# CH32V407VET-R0.net
KiCad netlist of a schematic drawn in Altium Designer
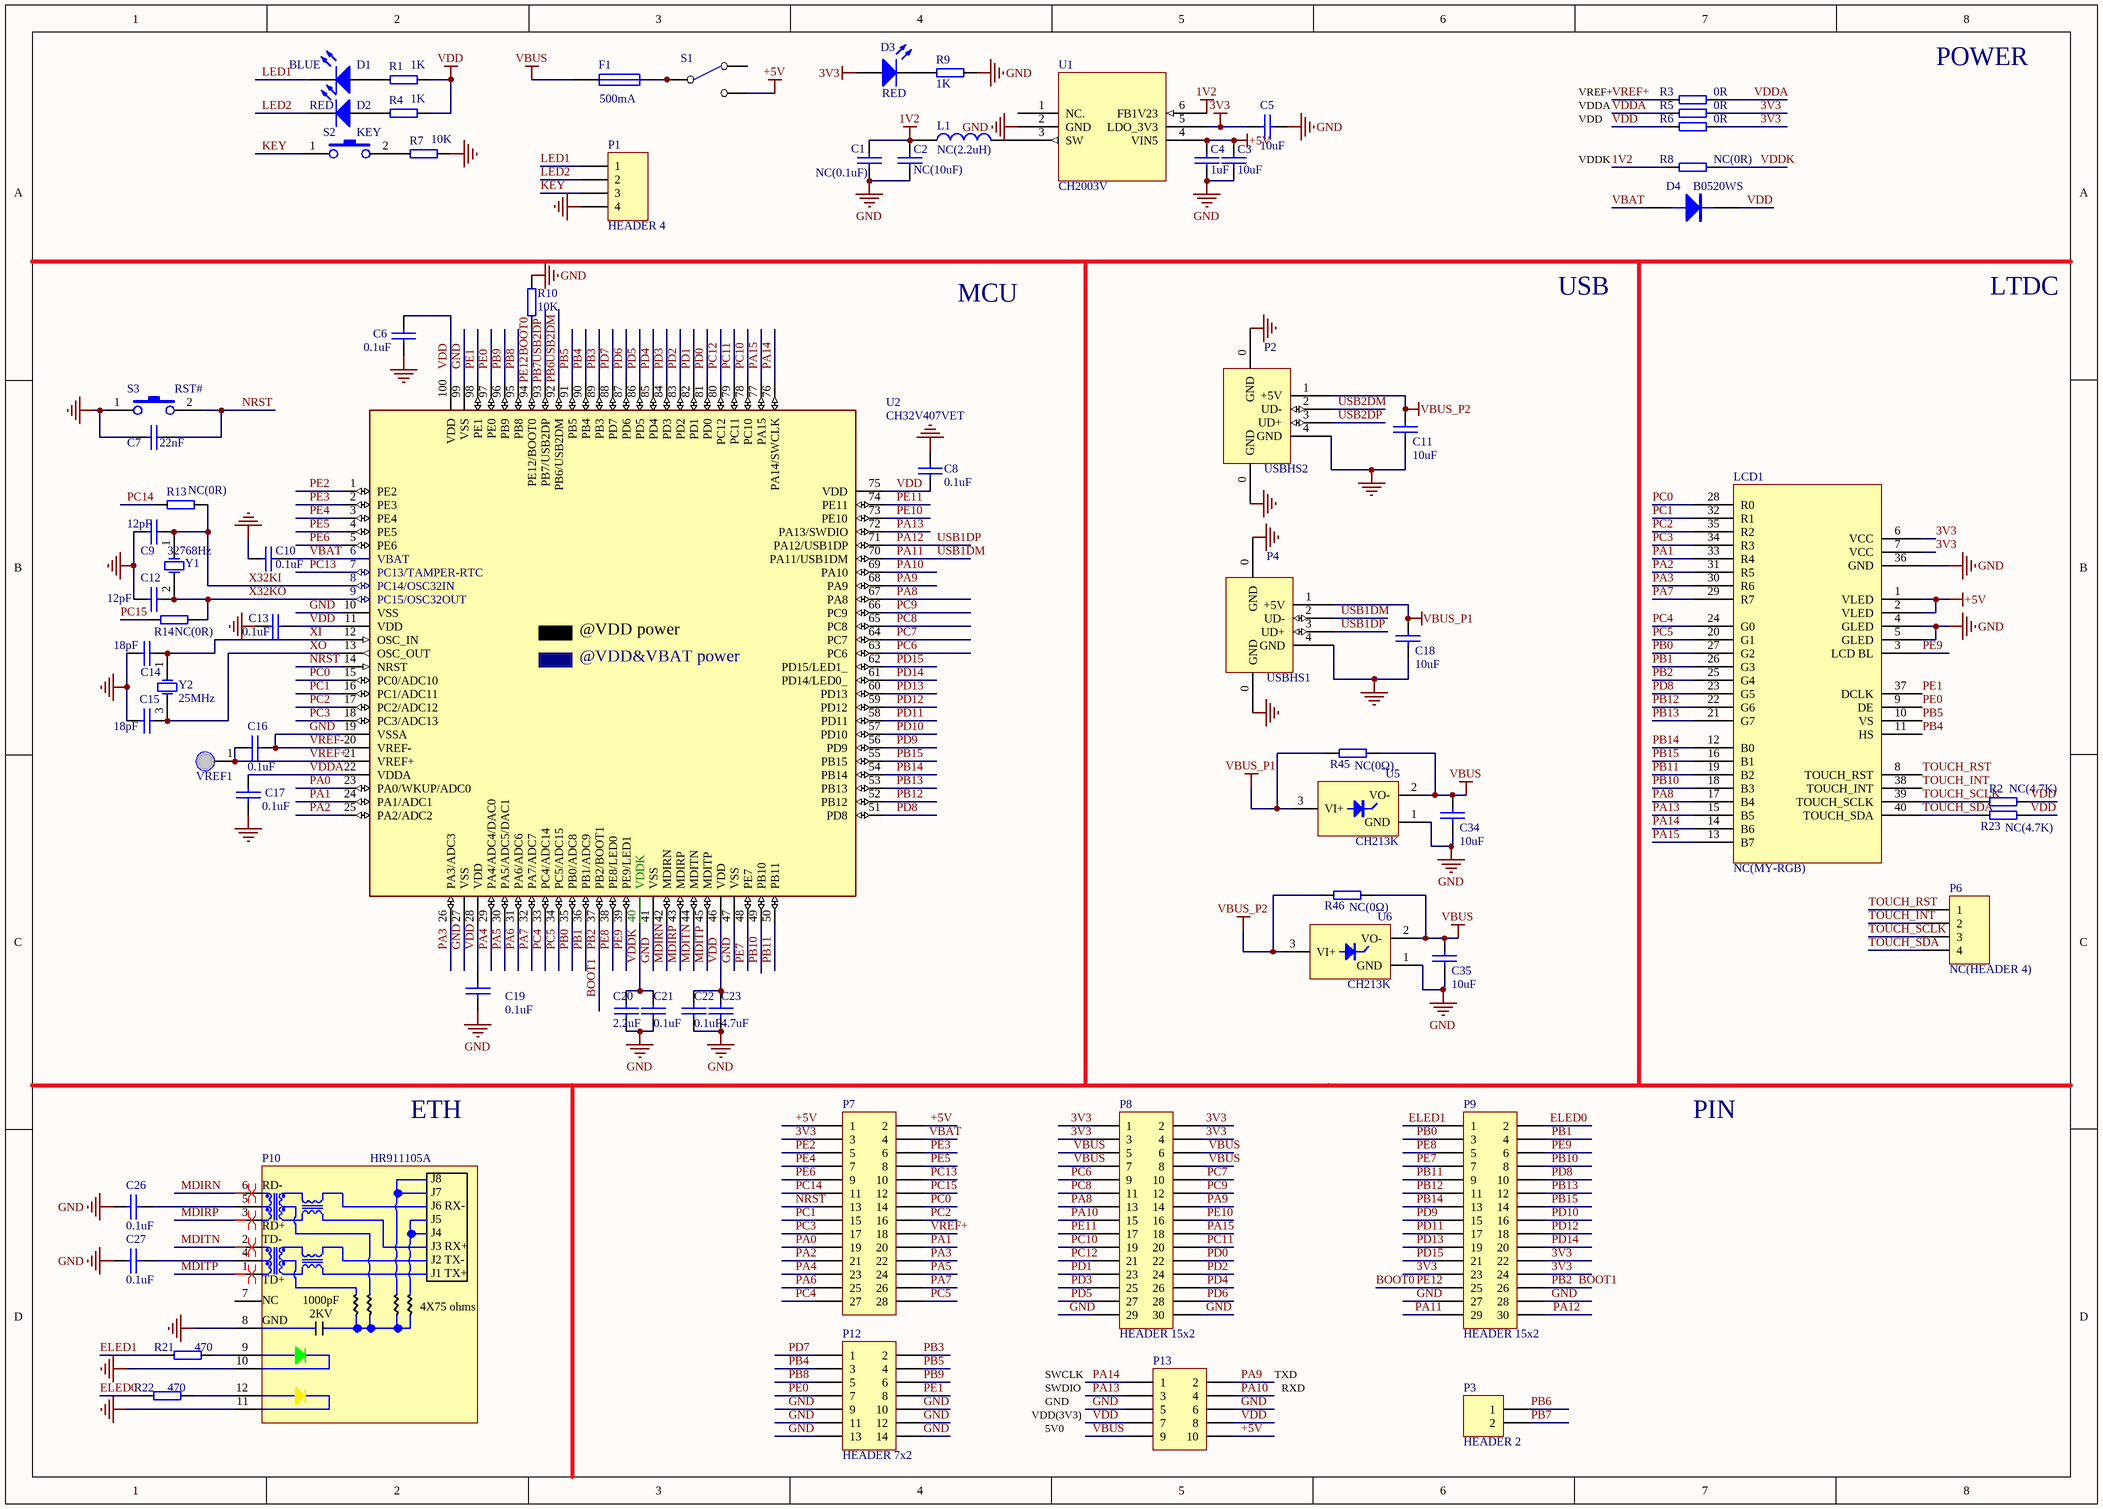
[diagram p0: CH32V407VET-R0.SchDoc]

(export (version "E")
  (design (tool "Eeschema 10.0.6"))
  (components
    (comp (ref "C1")
      (value "NC(0.1uF)")
      (footprint "0402_C")
      (description "Capacitor")
      (libsource (lib "*") (part "CAP"))
    )
    (comp (ref "C2")
      (value "NC(10uF)")
      (footprint "0603_C")
      (description "Capacitor")
      (libsource (lib "") (part "CAP_1"))
    )
    (comp (ref "C3")
      (value "10uF")
      (footprint "0603_C")
      (description "Capacitor")
      (libsource (lib "") (part "CAP_1"))
    )
    (comp (ref "C4")
      (value "1uF")
      (footprint "0402_C")
      (description "Capacitor")
      (libsource (lib "*") (part "CAP"))
    )
    (comp (ref "C5")
      (value "10uF")
      (footprint "0603_C")
      (description "Capacitor")
      (libsource (lib "") (part "CAP_1"))
    )
    (comp (ref "C6")
      (value "0.1uF")
      (footprint "0402_C")
      (description "Capacitor")
      (libsource (lib "") (part "CAP_1"))
    )
    (comp (ref "C7")
      (value "22nF")
      (footprint "0402_C")
      (description "Capacitor")
      (libsource (lib "") (part "CAP_2"))
    )
    (comp (ref "C8")
      (value "0.1uF")
      (footprint "0402_C")
      (description "Capacitor")
      (libsource (lib "") (part "CAP_1"))
    )
    (comp (ref "C9")
      (value "12pF")
      (footprint "0402_C")
      (description "Capacitor")
      (libsource (lib "") (part "CAP_1"))
    )
    (comp (ref "C10")
      (value "0.1uF")
      (footprint "0402_C")
      (description "Capacitor")
      (libsource (lib "") (part "CAP_1"))
    )
    (comp (ref "C11")
      (value "10uF")
      (footprint "0603_C")
      (description "Capacitor")
      (libsource (lib "") (part "CAP_2"))
    )
    (comp (ref "C12")
      (value "12pF")
      (footprint "0402_C")
      (description "Capacitor")
      (libsource (lib "") (part "CAP_1"))
    )
    (comp (ref "C13")
      (value "0.1uF")
      (footprint "0402_C")
      (description "Capacitor")
      (libsource (lib "") (part "CAP_1"))
    )
    (comp (ref "C14")
      (value "18pF")
      (footprint "0402_C")
      (description "Capacitor")
      (libsource (lib "") (part "CAP_1"))
    )
    (comp (ref "C15")
      (value "18pF")
      (footprint "0402_C")
      (description "Capacitor")
      (libsource (lib "") (part "CAP_1"))
    )
    (comp (ref "C16")
      (value "0.1uF")
      (footprint "0402_C")
      (description "Capacitor")
      (libsource (lib "") (part "CAP_1"))
    )
    (comp (ref "C17")
      (value "0.1uF")
      (footprint "0402_C")
      (description "Capacitor")
      (libsource (lib "") (part "CAP_1"))
    )
    (comp (ref "C18")
      (value "10uF")
      (footprint "0603_C")
      (description "Capacitor")
      (libsource (lib "") (part "CAP_2"))
    )
    (comp (ref "C19")
      (value "0.1uF")
      (footprint "0402_C")
      (description "Capacitor")
      (libsource (lib "") (part "CAP_1"))
    )
    (comp (ref "C20")
      (value "2.2uF")
      (footprint "0402_C")
      (description "Capacitor")
      (libsource (lib "") (part "CAP_1"))
    )
    (comp (ref "C21")
      (value "0.1uF")
      (footprint "0402_C")
      (description "Capacitor")
      (libsource (lib "") (part "CAP_1"))
    )
    (comp (ref "C22")
      (value "0.1uF")
      (footprint "0402_C")
      (description "Capacitor")
      (libsource (lib "") (part "CAP_1"))
    )
    (comp (ref "C23")
      (value "4.7uF")
      (footprint "0402_C")
      (description "Capacitor")
      (libsource (lib "") (part "CAP_1"))
    )
    (comp (ref "C26")
      (value "0.1uF")
      (footprint "0402_C")
      (description "Capacitor")
      (libsource (lib "wch_sch_others") (part "CAP"))
    )
    (comp (ref "C27")
      (value "0.1uF")
      (footprint "0402_C")
      (description "Capacitor")
      (libsource (lib "wch_sch_others") (part "CAP"))
    )
    (comp (ref "C34")
      (value "10uF")
      (footprint "0603_C")
      (description "Capacitor")
      (libsource (lib "") (part "CAP_2"))
    )
    (comp (ref "C35")
      (value "10uF")
      (footprint "0603_C")
      (description "Capacitor")
      (libsource (lib "") (part "CAP_2"))
    )
    (comp (ref "D1")
      (value "BLUE")
      (footprint "0603+")
      (description "Typical INFRARED GaAs LED")
      (fields (field (name "PUBLISHER") "Altium Limited"))
      (libsource (lib "*") (part "LED0"))
    )
    (comp (ref "D2")
      (value "RED")
      (footprint "0603+")
      (description "Typical INFRARED GaAs LED")
      (fields (field (name "PUBLISHER") "Altium Limited"))
      (libsource (lib "*") (part "LED0"))
    )
    (comp (ref "D3")
      (value "RED")
      (footprint "0603+")
      (description "Typical INFRARED GaAs LED")
      (fields (field (name "PUBLISHER") "Altium Limited"))
      (libsource (lib "*") (part "LED0"))
    )
    (comp (ref "D4")
      (value "B0520WS")
      (footprint "SOD-323")
      (description "Diode")
      (libsource (lib "*") (part "DIODE"))
    )
    (comp (ref "F1")
      (value "500mA")
      (footprint "0603")
      (description "Fuse")
      (libsource (lib "wch_sch_others") (part "FUSE1"))
    )
    (comp (ref "L1") (value "NC(2.2uH)") (footprint "CD32") (libsource (lib "*") (part "INDUCTOR")))
    (comp (ref "LCD1")
      (value "NC(MY-RGB)")
      (footprint "FPC40P-0.5-FK750M3")
      (libsource (lib "MY-显示") (part "MY-RGB"))
    )
    (comp (ref "P1")
      (value "HEADER 4")
      (footprint "SIP4-2.54mm")
      (description "Header, 4-Pin")
      (libsource (lib "wch_sch_others") (part "HEADER 4"))
    )
    (comp (ref "P2")
      (value "USBHS2")
      (footprint "USBAF")
      (description "USB Port")
      (libsource (lib "*") (part "USB"))
    )
    (comp (ref "P3")
      (value "HEADER 2")
      (footprint "MYPCB:SIP2-2.54mm")
      (description "Header, 2-Pin")
      (libsource (lib "wch_sch_others") (part "HEADER 2"))
    )
    (comp (ref "P4")
      (value "USBHS1")
      (footprint "USBAF")
      (description "USB Port")
      (libsource (lib "*") (part "USB"))
    )
    (comp (ref "P6")
      (value "NC(HEADER 4)")
      (footprint "SIP4-2.54mm")
      (description "Header, 4-Pin")
      (libsource (lib "wch_sch_others") (part "HEADER 4"))
    )
    (comp (ref "P7")
      (value "HEADER 14x2")
      (footprint "MYPCB:IDC28-2.54MM")
      (description "Header, 14-Pin, Dual row")
      (libsource (lib "wch_sch_others") (part "HEADER 14x2"))
    )
    (comp (ref "P8")
      (value "HEADER 15x2")
      (footprint "MYPCB:IDC30-2.54MM")
      (description "Header, 15-Pin, Dual row")
      (libsource (lib "wch_sch_others") (part "HEADER 15x2"))
    )
    (comp (ref "P9")
      (value "HEADER 15x2")
      (footprint "MYPCB:IDC30-2.54MM")
      (description "Header, 15-Pin, Dual row")
      (libsource (lib "wch_sch_others") (part "HEADER 15x2"))
    )
    (comp (ref "P10") (value "HR911105A") (footprint "HR911105A") (libsource (lib "*") (part "HR911105A")))
    (comp (ref "P12")
      (value "HEADER 7x2")
      (footprint "MYPCB:IDC14-2.54mm")
      (description "Header, 7-Pin, Dual row")
      (libsource (lib "wch_sch_others") (part "HEADER 7x2"))
    )
    (comp (ref "P13")
      (value "LINK")
      (footprint "IDC10-2.54mm")
      (description "Header, 5-Pin, Dual row, Right Angle")
      (fields (field (name "PUBLISHER") "Altium Limited"))
      (libsource (lib "Miscellaneous Connectors") (part "Header 5X2H"))
    )
    (comp (ref "R1") (value "1K") (footprint "0402") (libsource (lib "wch_sch_others") (part "RES")))
    (comp (ref "R2") (value "NC(4.7K)") (footprint "0402") (libsource (lib "wch_sch_others") (part "RES")))
    (comp (ref "R3") (value "0R") (footprint "0402") (libsource (lib "*") (part "R")))
    (comp (ref "R4") (value "1K") (footprint "0402") (libsource (lib "wch_sch_others") (part "RES")))
    (comp (ref "R5") (value "0R") (footprint "0402") (libsource (lib "*") (part "R")))
    (comp (ref "R6") (value "0R") (footprint "0402") (libsource (lib "*") (part "R")))
    (comp (ref "R7") (value "10K") (footprint "0402") (libsource (lib "wch_sch_others") (part "RES")))
    (comp (ref "R8") (value "NC(0R)") (footprint "0402") (libsource (lib "*") (part "R")))
    (comp (ref "R9") (value "1K") (footprint "0402") (libsource (lib "wch_sch_others") (part "RES")))
    (comp (ref "R10") (value "10K") (footprint "0402") (libsource (lib "wch_sch_others") (part "RES")))
    (comp (ref "R13") (value "NC(0R)") (footprint "0402") (libsource (lib "wch_sch_others") (part "RES")))
    (comp (ref "R14") (value "NC(0R)") (footprint "0402") (libsource (lib "wch_sch_others") (part "RES")))
    (comp (ref "R21") (value "470") (footprint "0402") (libsource (lib "wch_sch_others") (part "RES")))
    (comp (ref "R22") (value "470") (footprint "0402") (libsource (lib "wch_sch_others") (part "RES")))
    (comp (ref "R23") (value "NC(4.7K)") (footprint "0402") (libsource (lib "wch_sch_others") (part "RES")))
    (comp (ref "R45") (value "NC(0Ω)") (footprint "0402") (libsource (lib "wch_sch_others") (part "RES")))
    (comp (ref "R46") (value "NC(0Ω)") (footprint "0402") (libsource (lib "wch_sch_others") (part "RES")))
    (comp (ref "S1") (value "SW SPDT") (footprint "SW1") (libsource (lib "*") (part "SW SPDT")))
    (comp (ref "S2")
      (value "KEY")
      (footprint "SMD_6.1x3.65x2.5mm-KEY")
      (libsource (lib "wch_sch_others") (part "KEY1"))
    )
    (comp (ref "S3")
      (value "RST#")
      (footprint "SMD_6.1x3.65x2.5mm-KEY")
      (libsource (lib "wch_sch_others") (part "KEY1"))
    )
    (comp (ref "U1")
      (value "CH2003V")
      (footprint "SOT-23-6")
      (description "Step-Down DC-DC Converter, 5V input, 1.23V * 800mA output, with LDO 3.3V * 200mA")
      (libsource (lib "CHXXX") (part "CH2003V"))
    )
    (comp (ref "U2")
      (value "CH32V407VET")
      (footprint "LQFP100")
      (description "RISC-V FPU HD-MCU, 175MHz, USB_480M, 100M Ethernet & Phy, CAN, DVP, ADC, DAC")
      (libsource (lib "CHXXX") (part "CH32V407VET"))
    )
    (comp (ref "U5")
      (value "CH213K")
      (footprint "SOT-23-3")
      (description "Ideal Diode 5V*1A")
      (libsource (lib "*") (part "CH213K"))
    )
    (comp (ref "U6")
      (value "CH213K")
      (footprint "SOT-23-3")
      (description "Ideal Diode 5V*1A")
      (libsource (lib "*") (part "CH213K"))
    )
    (comp (ref "VREF1")
      (value "PAD")
      (footprint "TESTPOINT1")
      (description "焊盘")
      (libsource (lib "wch_sch_others") (part "PAD"))
    )
    (comp (ref "Y1")
      (value "32768Hz")
      (footprint "FC-135")
      (description "Crystal Oscillator")
      (fields (field (name "PUBLISHER") "Altium Limited"))
      (libsource (lib "") (part "XTAL_1"))
    )
    (comp (ref "Y2")
      (value "25MHz")
      (footprint "XT3225")
      (description "Crystal Oscillator")
      (fields (field (name "PUBLISHER") "Altium Limited"))
      (libsource (lib "*") (part "XTAL"))
    )
  )
  (nets
    (net (code "1") (name "+5V") (class "Default")
      (node (ref "C3") (pin "2") (pinfunction "2_2") (pintype "passive"))
      (node (ref "C4") (pin "2") (pinfunction "2_2") (pintype "passive"))
      (node (ref "LCD1") (pin "1") (pinfunction "VLED_1") (pintype "passive"))
      (node (ref "LCD1") (pin "2") (pinfunction "VLED_2") (pintype "passive"))
      (node (ref "P13") (pin "10") (pinfunction "10_10") (pintype "passive"))
      (node (ref "P7") (pin "1") (pinfunction "1_1") (pintype "passive"))
      (node (ref "P7") (pin "2") (pinfunction "2_2") (pintype "passive"))
      (node (ref "S1") (pin "2") (pinfunction "NC_2") (pintype "passive"))
      (node (ref "U1") (pin "4") (pinfunction "VIN5_4") (pintype "power_in"))
    )
    (net (code "3") (name "/BOOT0") (class "Default")
      (node (ref "P9") (pin "25") (pinfunction "25_25") (pintype "passive"))
      (node (ref "R10") (pin "2") (pintype "passive"))
      (node (ref "U2") (pin "94") (pinfunction "PE12/BOOT0_94") (pintype "bidirectional"))
    )
    (net (code "4") (name "/BOOT1") (class "Default")
      (node (ref "LCD1") (pin "25") (pinfunction "G4_25") (pintype "passive"))
      (node (ref "P9") (pin "26") (pinfunction "26_26") (pintype "passive"))
      (node (ref "U2") (pin "37") (pinfunction "PB2/BOOT1_37") (pintype "bidirectional"))
    )
    (net (code "5") (name "/ELED0") (class "Default")
      (node (ref "P9") (pin "2") (pinfunction "2_2") (pintype "passive"))
      (node (ref "R22") (pin "1") (pintype "passive"))
    )
    (net (code "6") (name "/ELED1") (class "Default")
      (node (ref "P9") (pin "1") (pinfunction "1_1") (pintype "passive"))
      (node (ref "R21") (pin "1") (pintype "passive"))
    )
    (net (code "7") (name "/KEY") (class "Default")
      (node (ref "P1") (pin "3") (pinfunction "3_3") (pintype "passive"))
      (node (ref "S2") (pin "1") (pinfunction "1_1") (pintype "passive"))
    )
    (net (code "8") (name "/LED1") (class "Default")
      (node (ref "D1") (pin "2") (pinfunction "K_2") (pintype "passive"))
      (node (ref "P1") (pin "1") (pinfunction "1_1") (pintype "passive"))
    )
    (net (code "9") (name "/LED2") (class "Default")
      (node (ref "D2") (pin "2") (pinfunction "K_2") (pintype "passive"))
      (node (ref "P1") (pin "2") (pinfunction "2_2") (pintype "passive"))
    )
    (net (code "10") (name "/MDIRN") (class "Default")
      (node (ref "P10") (pin "6") (pintype "passive"))
      (node (ref "U2") (pin "42") (pinfunction "MDIRN_42") (pintype "bidirectional"))
    )
    (net (code "11") (name "/MDIRP") (class "Default")
      (node (ref "P10") (pin "3") (pintype "passive"))
      (node (ref "U2") (pin "43") (pinfunction "MDIRP_43") (pintype "bidirectional"))
    )
    (net (code "12") (name "/MDITN") (class "Default")
      (node (ref "P10") (pin "2") (pintype "passive"))
      (node (ref "U2") (pin "44") (pinfunction "MDITN_44") (pintype "bidirectional"))
    )
    (net (code "13") (name "/MDITP") (class "Default")
      (node (ref "P10") (pin "1") (pintype "passive"))
      (node (ref "U2") (pin "45") (pinfunction "MDITP_45") (pintype "bidirectional"))
    )
    (net (code "14") (name "/NRST") (class "Default")
      (node (ref "C7") (pin "2") (pinfunction "2_2") (pintype "passive"))
      (node (ref "P7") (pin "13") (pinfunction "13_13") (pintype "passive"))
      (node (ref "S3") (pin "2") (pinfunction "2_2") (pintype "passive"))
      (node (ref "U2") (pin "14") (pinfunction "NRST_14") (pintype "input"))
    )
    (net (code "15") (name "/PA0") (class "Default")
      (node (ref "P7") (pin "19") (pinfunction "19_19") (pintype "passive"))
      (node (ref "U2") (pin "23") (pinfunction "PA0/WKUP/ADC0_23") (pintype "bidirectional"))
    )
    (net (code "16") (name "/PA1") (class "Default")
      (node (ref "LCD1") (pin "33") (pinfunction "R4_33") (pintype "passive"))
      (node (ref "P7") (pin "20") (pinfunction "20_20") (pintype "passive"))
      (node (ref "U2") (pin "24") (pinfunction "PA1/ADC1_24") (pintype "bidirectional"))
    )
    (net (code "17") (name "/PA2") (class "Default")
      (node (ref "LCD1") (pin "31") (pinfunction "R5_31") (pintype "passive"))
      (node (ref "P7") (pin "21") (pinfunction "21_21") (pintype "passive"))
      (node (ref "U2") (pin "25") (pinfunction "PA2/ADC2_25") (pintype "bidirectional"))
    )
    (net (code "18") (name "/PA3") (class "Default")
      (node (ref "LCD1") (pin "30") (pinfunction "R6_30") (pintype "passive"))
      (node (ref "P7") (pin "22") (pinfunction "22_22") (pintype "passive"))
      (node (ref "U2") (pin "26") (pinfunction "PA3/ADC3_26") (pintype "bidirectional"))
    )
    (net (code "19") (name "/PA4") (class "Default")
      (node (ref "P7") (pin "23") (pinfunction "23_23") (pintype "passive"))
      (node (ref "U2") (pin "29") (pinfunction "PA4/ADC4/DAC0_29") (pintype "bidirectional"))
    )
    (net (code "20") (name "/PA5") (class "Default")
      (node (ref "P7") (pin "24") (pinfunction "24_24") (pintype "passive"))
      (node (ref "U2") (pin "30") (pinfunction "PA5/ADC5/DAC1_30") (pintype "bidirectional"))
    )
    (net (code "21") (name "/PA6") (class "Default")
      (node (ref "P7") (pin "25") (pinfunction "25_25") (pintype "passive"))
      (node (ref "U2") (pin "31") (pinfunction "PA6/ADC6_31") (pintype "bidirectional"))
    )
    (net (code "22") (name "/PA7") (class "Default")
      (node (ref "LCD1") (pin "29") (pinfunction "R7_29") (pintype "passive"))
      (node (ref "P7") (pin "26") (pinfunction "26_26") (pintype "passive"))
      (node (ref "U2") (pin "32") (pinfunction "PA7/ADC7_32") (pintype "bidirectional"))
    )
    (net (code "23") (name "/PA8") (class "Default")
      (node (ref "LCD1") (pin "17") (pinfunction "B4_17") (pintype "passive"))
      (node (ref "P8") (pin "13") (pinfunction "13_13") (pintype "passive"))
      (node (ref "U2") (pin "67") (pinfunction "PA8_67") (pintype "bidirectional"))
    )
    (net (code "24") (name "/PA9") (class "Default")
      (node (ref "P13") (pin "2") (pinfunction "2_2") (pintype "passive"))
      (node (ref "P8") (pin "14") (pinfunction "14_14") (pintype "passive"))
      (node (ref "U2") (pin "68") (pinfunction "PA9_68") (pintype "bidirectional"))
    )
    (net (code "25") (name "/PA10") (class "Default")
      (node (ref "P13") (pin "4") (pinfunction "4_4") (pintype "passive"))
      (node (ref "P8") (pin "15") (pinfunction "15_15") (pintype "passive"))
      (node (ref "U2") (pin "69") (pinfunction "PA10_69") (pintype "bidirectional"))
    )
    (net (code "26") (name "/PA11") (class "Default")
      (node (ref "P4") (pin "2") (pinfunction "UD-_2") (pintype "bidirectional"))
      (node (ref "P9") (pin "29") (pinfunction "29_29") (pintype "passive"))
      (node (ref "U2") (pin "70") (pinfunction "PA11/USB1DM_70") (pintype "bidirectional"))
    )
    (net (code "27") (name "/PA12") (class "Default")
      (node (ref "P4") (pin "3") (pinfunction "UD+_3") (pintype "bidirectional"))
      (node (ref "P9") (pin "30") (pinfunction "30_30") (pintype "passive"))
      (node (ref "U2") (pin "71") (pinfunction "PA12/USB1DP_71") (pintype "bidirectional"))
    )
    (net (code "28") (name "/PA13") (class "Default")
      (node (ref "LCD1") (pin "15") (pinfunction "B5_15") (pintype "passive"))
      (node (ref "P13") (pin "3") (pinfunction "3_3") (pintype "passive"))
      (node (ref "U2") (pin "72") (pinfunction "PA13/SWDIO_72") (pintype "bidirectional"))
    )
    (net (code "29") (name "/PA14") (class "Default")
      (node (ref "LCD1") (pin "14") (pinfunction "B6_14") (pintype "passive"))
      (node (ref "P13") (pin "1") (pinfunction "1_1") (pintype "passive"))
      (node (ref "U2") (pin "76") (pinfunction "PA14/SWCLK_76") (pintype "bidirectional"))
    )
    (net (code "30") (name "/PA15") (class "Default")
      (node (ref "LCD1") (pin "13") (pinfunction "B7_13") (pintype "passive"))
      (node (ref "P8") (pin "18") (pinfunction "18_18") (pintype "passive"))
      (node (ref "U2") (pin "77") (pinfunction "PA15_77") (pintype "bidirectional"))
    )
    (net (code "31") (name "/PB0") (class "Default")
      (node (ref "LCD1") (pin "27") (pinfunction "G2_27") (pintype "passive"))
      (node (ref "P9") (pin "3") (pinfunction "3_3") (pintype "passive"))
      (node (ref "U2") (pin "35") (pinfunction "PB0/ADC8_35") (pintype "bidirectional"))
    )
    (net (code "32") (name "/PB1") (class "Default")
      (node (ref "LCD1") (pin "26") (pinfunction "G3_26") (pintype "passive"))
      (node (ref "P9") (pin "4") (pinfunction "4_4") (pintype "passive"))
      (node (ref "U2") (pin "36") (pinfunction "PB1/ADC9_36") (pintype "bidirectional"))
    )
    (net (code "33") (name "/PB3") (class "Default")
      (node (ref "P12") (pin "2") (pinfunction "2_2") (pintype "passive"))
      (node (ref "U2") (pin "89") (pinfunction "PB3_89") (pintype "bidirectional"))
    )
    (net (code "34") (name "/PB4") (class "Default")
      (node (ref "LCD1") (pin "11") (pinfunction "HS_11") (pintype "passive"))
      (node (ref "P12") (pin "3") (pinfunction "3_3") (pintype "passive"))
      (node (ref "U2") (pin "90") (pinfunction "PB4_90") (pintype "bidirectional"))
    )
    (net (code "35") (name "/PB5") (class "Default")
      (node (ref "LCD1") (pin "10") (pinfunction "VS_10") (pintype "passive"))
      (node (ref "P12") (pin "4") (pinfunction "4_4") (pintype "passive"))
      (node (ref "U2") (pin "91") (pinfunction "PB5_91") (pintype "bidirectional"))
    )
    (net (code "36") (name "/PB6") (class "Default")
      (node (ref "P2") (pin "2") (pinfunction "UD-_2") (pintype "bidirectional"))
      (node (ref "P3") (pin "1") (pinfunction "1_1") (pintype "passive"))
      (node (ref "U2") (pin "92") (pinfunction "PB6/USB2DM_92") (pintype "bidirectional"))
    )
    (net (code "37") (name "/PB7") (class "Default")
      (node (ref "P2") (pin "3") (pinfunction "UD+_3") (pintype "bidirectional"))
      (node (ref "P3") (pin "2") (pinfunction "2_2") (pintype "passive"))
      (node (ref "U2") (pin "93") (pinfunction "PB7/USB2DP_93") (pintype "bidirectional"))
    )
    (net (code "38") (name "/PB8") (class "Default")
      (node (ref "P12") (pin "5") (pinfunction "5_5") (pintype "passive"))
      (node (ref "U2") (pin "95") (pinfunction "PB8_95") (pintype "bidirectional"))
    )
    (net (code "39") (name "/PB9") (class "Default")
      (node (ref "P12") (pin "6") (pinfunction "6_6") (pintype "passive"))
      (node (ref "U2") (pin "96") (pinfunction "PB9_96") (pintype "bidirectional"))
    )
    (net (code "40") (name "/PB10") (class "Default")
      (node (ref "LCD1") (pin "18") (pinfunction "B3_18") (pintype "passive"))
      (node (ref "P9") (pin "8") (pinfunction "8_8") (pintype "passive"))
      (node (ref "U2") (pin "49") (pinfunction "PB10_49") (pintype "bidirectional"))
    )
    (net (code "41") (name "/PB11") (class "Default")
      (node (ref "LCD1") (pin "19") (pinfunction "B2_19") (pintype "passive"))
      (node (ref "P9") (pin "9") (pinfunction "9_9") (pintype "passive"))
      (node (ref "U2") (pin "50") (pinfunction "PB11_50") (pintype "bidirectional"))
    )
    (net (code "42") (name "/PB12") (class "Default")
      (node (ref "LCD1") (pin "22") (pinfunction "G6_22") (pintype "passive"))
      (node (ref "P9") (pin "11") (pinfunction "11_11") (pintype "passive"))
      (node (ref "U2") (pin "52") (pinfunction "PB12_52") (pintype "bidirectional"))
    )
    (net (code "43") (name "/PB13") (class "Default")
      (node (ref "LCD1") (pin "21") (pinfunction "G7_21") (pintype "passive"))
      (node (ref "P9") (pin "12") (pinfunction "12_12") (pintype "passive"))
      (node (ref "U2") (pin "53") (pinfunction "PB13_53") (pintype "bidirectional"))
    )
    (net (code "44") (name "/PB14") (class "Default")
      (node (ref "LCD1") (pin "12") (pinfunction "B0_12") (pintype "passive"))
      (node (ref "P9") (pin "13") (pinfunction "13_13") (pintype "passive"))
      (node (ref "U2") (pin "54") (pinfunction "PB14_54") (pintype "bidirectional"))
    )
    (net (code "45") (name "/PB15") (class "Default")
      (node (ref "LCD1") (pin "16") (pinfunction "B1_16") (pintype "passive"))
      (node (ref "P9") (pin "14") (pinfunction "14_14") (pintype "passive"))
      (node (ref "U2") (pin "55") (pinfunction "PB15_55") (pintype "bidirectional"))
    )
    (net (code "46") (name "/PC0") (class "Default")
      (node (ref "LCD1") (pin "28") (pinfunction "R0_28") (pintype "passive"))
      (node (ref "P7") (pin "14") (pinfunction "14_14") (pintype "passive"))
      (node (ref "U2") (pin "15") (pinfunction "PC0/ADC10_15") (pintype "bidirectional"))
    )
    (net (code "47") (name "/PC1") (class "Default")
      (node (ref "LCD1") (pin "32") (pinfunction "R1_32") (pintype "passive"))
      (node (ref "P7") (pin "15") (pinfunction "15_15") (pintype "passive"))
      (node (ref "U2") (pin "16") (pinfunction "PC1/ADC11_16") (pintype "bidirectional"))
    )
    (net (code "48") (name "/PC2") (class "Default")
      (node (ref "LCD1") (pin "35") (pinfunction "R2_35") (pintype "passive"))
      (node (ref "P7") (pin "16") (pinfunction "16_16") (pintype "passive"))
      (node (ref "U2") (pin "17") (pinfunction "PC2/ADC12_17") (pintype "bidirectional"))
    )
    (net (code "49") (name "/PC3") (class "Default")
      (node (ref "LCD1") (pin "34") (pinfunction "R3_34") (pintype "passive"))
      (node (ref "P7") (pin "17") (pinfunction "17_17") (pintype "passive"))
      (node (ref "U2") (pin "18") (pinfunction "PC3/ADC13_18") (pintype "bidirectional"))
    )
    (net (code "50") (name "/PC4") (class "Default")
      (node (ref "LCD1") (pin "24") (pinfunction "G0_24") (pintype "passive"))
      (node (ref "P7") (pin "27") (pinfunction "27_27") (pintype "passive"))
      (node (ref "U2") (pin "33") (pinfunction "PC4/ADC14_33") (pintype "bidirectional"))
    )
    (net (code "51") (name "/PC5") (class "Default")
      (node (ref "LCD1") (pin "20") (pinfunction "G1_20") (pintype "passive"))
      (node (ref "P7") (pin "28") (pinfunction "28_28") (pintype "passive"))
      (node (ref "U2") (pin "34") (pinfunction "PC5/ADC15_34") (pintype "bidirectional"))
    )
    (net (code "52") (name "/PC6") (class "Default")
      (node (ref "P8") (pin "9") (pinfunction "9_9") (pintype "passive"))
      (node (ref "U2") (pin "63") (pinfunction "PC6_63") (pintype "bidirectional"))
    )
    (net (code "53") (name "/PC7") (class "Default")
      (node (ref "P8") (pin "10") (pinfunction "10_10") (pintype "passive"))
      (node (ref "U2") (pin "64") (pinfunction "PC7_64") (pintype "bidirectional"))
    )
    (net (code "54") (name "/PC8") (class "Default")
      (node (ref "P8") (pin "11") (pinfunction "11_11") (pintype "passive"))
      (node (ref "U2") (pin "65") (pinfunction "PC8_65") (pintype "bidirectional"))
    )
    (net (code "55") (name "/PC9") (class "Default")
      (node (ref "P8") (pin "12") (pinfunction "12_12") (pintype "passive"))
      (node (ref "U2") (pin "66") (pinfunction "PC9_66") (pintype "bidirectional"))
    )
    (net (code "56") (name "/PC10") (class "Default")
      (node (ref "P8") (pin "19") (pinfunction "19_19") (pintype "passive"))
      (node (ref "U2") (pin "78") (pinfunction "PC10_78") (pintype "bidirectional"))
    )
    (net (code "57") (name "/PC11") (class "Default")
      (node (ref "P8") (pin "20") (pinfunction "20_20") (pintype "passive"))
      (node (ref "U2") (pin "79") (pinfunction "PC11_79") (pintype "bidirectional"))
    )
    (net (code "58") (name "/PC12") (class "Default")
      (node (ref "P8") (pin "21") (pinfunction "21_21") (pintype "passive"))
      (node (ref "U2") (pin "80") (pinfunction "PC12_80") (pintype "bidirectional"))
    )
    (net (code "59") (name "/PC13") (class "Default")
      (node (ref "P7") (pin "10") (pinfunction "10_10") (pintype "passive"))
      (node (ref "U2") (pin "7") (pinfunction "PC13/TAMPER-RTC_7") (pintype "bidirectional"))
    )
    (net (code "60") (name "/PC14") (class "Default")
      (node (ref "P7") (pin "11") (pinfunction "11_11") (pintype "passive"))
      (node (ref "R13") (pin "1") (pintype "passive"))
    )
    (net (code "61") (name "/PC15") (class "Default")
      (node (ref "P7") (pin "12") (pinfunction "12_12") (pintype "passive"))
      (node (ref "R14") (pin "1") (pintype "passive"))
    )
    (net (code "62") (name "/PD0") (class "Default")
      (node (ref "P8") (pin "22") (pinfunction "22_22") (pintype "passive"))
      (node (ref "U2") (pin "81") (pinfunction "PD0_81") (pintype "bidirectional"))
    )
    (net (code "63") (name "/PD1") (class "Default")
      (node (ref "P8") (pin "23") (pinfunction "23_23") (pintype "passive"))
      (node (ref "U2") (pin "82") (pinfunction "PD1_82") (pintype "bidirectional"))
    )
    (net (code "64") (name "/PD2") (class "Default")
      (node (ref "P8") (pin "24") (pinfunction "24_24") (pintype "passive"))
      (node (ref "U2") (pin "83") (pinfunction "PD2_83") (pintype "bidirectional"))
    )
    (net (code "65") (name "/PD3") (class "Default")
      (node (ref "P8") (pin "25") (pinfunction "25_25") (pintype "passive"))
      (node (ref "U2") (pin "84") (pinfunction "PD3_84") (pintype "bidirectional"))
    )
    (net (code "66") (name "/PD4") (class "Default")
      (node (ref "P8") (pin "26") (pinfunction "26_26") (pintype "passive"))
      (node (ref "U2") (pin "85") (pinfunction "PD4_85") (pintype "bidirectional"))
    )
    (net (code "67") (name "/PD5") (class "Default")
      (node (ref "P8") (pin "27") (pinfunction "27_27") (pintype "passive"))
      (node (ref "U2") (pin "86") (pinfunction "PD5_86") (pintype "bidirectional"))
    )
    (net (code "68") (name "/PD6") (class "Default")
      (node (ref "P8") (pin "28") (pinfunction "28_28") (pintype "passive"))
      (node (ref "U2") (pin "87") (pinfunction "PD6_87") (pintype "bidirectional"))
    )
    (net (code "69") (name "/PD7") (class "Default")
      (node (ref "P12") (pin "1") (pinfunction "1_1") (pintype "passive"))
      (node (ref "U2") (pin "88") (pinfunction "PD7_88") (pintype "bidirectional"))
    )
    (net (code "70") (name "/PD8") (class "Default")
      (node (ref "LCD1") (pin "23") (pinfunction "G5_23") (pintype "passive"))
      (node (ref "P9") (pin "10") (pinfunction "10_10") (pintype "passive"))
      (node (ref "U2") (pin "51") (pinfunction "PD8_51") (pintype "bidirectional"))
    )
    (net (code "71") (name "/PD9") (class "Default")
      (node (ref "P9") (pin "15") (pinfunction "15_15") (pintype "passive"))
      (node (ref "U2") (pin "56") (pinfunction "PD9_56") (pintype "bidirectional"))
    )
    (net (code "72") (name "/PD10") (class "Default")
      (node (ref "P9") (pin "16") (pinfunction "16_16") (pintype "passive"))
      (node (ref "U2") (pin "57") (pinfunction "PD10_57") (pintype "bidirectional"))
    )
    (net (code "73") (name "/PD11") (class "Default")
      (node (ref "P9") (pin "17") (pinfunction "17_17") (pintype "passive"))
      (node (ref "U2") (pin "58") (pinfunction "PD11_58") (pintype "bidirectional"))
    )
    (net (code "74") (name "/PD12") (class "Default")
      (node (ref "P9") (pin "18") (pinfunction "18_18") (pintype "passive"))
      (node (ref "U2") (pin "59") (pinfunction "PD12_59") (pintype "bidirectional"))
    )
    (net (code "75") (name "/PD13") (class "Default")
      (node (ref "P9") (pin "19") (pinfunction "19_19") (pintype "passive"))
      (node (ref "U2") (pin "60") (pinfunction "PD13_60") (pintype "bidirectional"))
    )
    (net (code "76") (name "/PD14") (class "Default")
      (node (ref "P9") (pin "20") (pinfunction "20_20") (pintype "passive"))
      (node (ref "U2") (pin "61") (pinfunction "PD14/LED0__61") (pintype "bidirectional"))
    )
    (net (code "77") (name "/PD15") (class "Default")
      (node (ref "P9") (pin "21") (pinfunction "21_21") (pintype "passive"))
      (node (ref "U2") (pin "62") (pinfunction "PD15/LED1__62") (pintype "bidirectional"))
    )
    (net (code "78") (name "/PE0") (class "Default")
      (node (ref "LCD1") (pin "9") (pinfunction "DE_9") (pintype "passive"))
      (node (ref "P12") (pin "7") (pinfunction "7_7") (pintype "passive"))
      (node (ref "U2") (pin "97") (pinfunction "PE0_97") (pintype "bidirectional"))
    )
    (net (code "79") (name "/PE1") (class "Default")
      (node (ref "LCD1") (pin "37") (pinfunction "DCLK_37") (pintype "passive"))
      (node (ref "P12") (pin "8") (pinfunction "8_8") (pintype "passive"))
      (node (ref "U2") (pin "98") (pinfunction "PE1_98") (pintype "bidirectional"))
    )
    (net (code "80") (name "/PE2") (class "Default")
      (node (ref "P7") (pin "5") (pinfunction "5_5") (pintype "passive"))
      (node (ref "U2") (pin "1") (pinfunction "PE2_1") (pintype "bidirectional"))
    )
    (net (code "81") (name "/PE3") (class "Default")
      (node (ref "P7") (pin "6") (pinfunction "6_6") (pintype "passive"))
      (node (ref "U2") (pin "2") (pinfunction "PE3_2") (pintype "bidirectional"))
    )
    (net (code "82") (name "/PE4") (class "Default")
      (node (ref "P7") (pin "7") (pinfunction "7_7") (pintype "passive"))
      (node (ref "U2") (pin "3") (pinfunction "PE4_3") (pintype "bidirectional"))
    )
    (net (code "83") (name "/PE5") (class "Default")
      (node (ref "P7") (pin "8") (pinfunction "8_8") (pintype "passive"))
      (node (ref "U2") (pin "4") (pinfunction "PE5_4") (pintype "bidirectional"))
    )
    (net (code "84") (name "/PE6") (class "Default")
      (node (ref "P7") (pin "9") (pinfunction "9_9") (pintype "passive"))
      (node (ref "U2") (pin "5") (pinfunction "PE6_5") (pintype "bidirectional"))
    )
    (net (code "85") (name "/PE7") (class "Default")
      (node (ref "P9") (pin "7") (pinfunction "7_7") (pintype "passive"))
      (node (ref "U2") (pin "48") (pinfunction "PE7_48") (pintype "bidirectional"))
    )
    (net (code "86") (name "/PE8") (class "Default")
      (node (ref "P9") (pin "5") (pinfunction "5_5") (pintype "passive"))
      (node (ref "U2") (pin "38") (pinfunction "PE8/LED0_38") (pintype "bidirectional"))
    )
    (net (code "87") (name "/PE9") (class "Default")
      (node (ref "LCD1") (pin "3") (pinfunction "LCD_BL_3") (pintype "passive"))
      (node (ref "P9") (pin "6") (pinfunction "6_6") (pintype "passive"))
      (node (ref "U2") (pin "39") (pinfunction "PE9/LED1_39") (pintype "bidirectional"))
    )
    (net (code "88") (name "/PE10") (class "Default")
      (node (ref "P8") (pin "16") (pinfunction "16_16") (pintype "passive"))
      (node (ref "U2") (pin "73") (pinfunction "PE10_73") (pintype "bidirectional"))
    )
    (net (code "89") (name "/PE11") (class "Default")
      (node (ref "P8") (pin "17") (pinfunction "17_17") (pintype "passive"))
      (node (ref "U2") (pin "74") (pinfunction "PE11_74") (pintype "bidirectional"))
    )
    (net (code "90") (name "/TOUCH_INT") (class "Default")
      (node (ref "LCD1") (pin "38") (pinfunction "TOUCH_INT_38") (pintype "passive"))
      (node (ref "P6") (pin "2") (pinfunction "2_2") (pintype "passive"))
    )
    (net (code "91") (name "/TOUCH_RST") (class "Default")
      (node (ref "LCD1") (pin "8") (pinfunction "TOUCH_RST_8") (pintype "passive"))
      (node (ref "P6") (pin "1") (pinfunction "1_1") (pintype "passive"))
    )
    (net (code "92") (name "/TOUCH_SCLK") (class "Default")
      (node (ref "LCD1") (pin "39") (pinfunction "TOUCH_SCLK_39") (pintype "passive"))
      (node (ref "P6") (pin "3") (pinfunction "3_3") (pintype "passive"))
      (node (ref "R2") (pin "2") (pintype "passive"))
    )
    (net (code "93") (name "/TOUCH_SDA") (class "Default")
      (node (ref "LCD1") (pin "40") (pinfunction "TOUCH_SDA_40") (pintype "passive"))
      (node (ref "P6") (pin "4") (pinfunction "4_4") (pintype "passive"))
      (node (ref "R23") (pin "2") (pintype "passive"))
    )
    (net (code "94") (name "/VBAT") (class "Default")
      (node (ref "C10") (pin "2") (pinfunction "2_2") (pintype "passive"))
      (node (ref "D4") (pin "1") (pinfunction "A_1") (pintype "passive"))
      (node (ref "P7") (pin "4") (pinfunction "4_4") (pintype "passive"))
      (node (ref "U2") (pin "6") (pinfunction "VBAT_6") (pintype "power_in"))
    )
    (net (code "95") (name "/VDDA") (class "Default")
      (node (ref "C17") (pin "1") (pinfunction "1_1") (pintype "passive"))
      (node (ref "R3") (pin "1") (pinfunction "1_1") (pintype "passive"))
      (node (ref "R5") (pin "2") (pinfunction "2_2") (pintype "passive"))
      (node (ref "U2") (pin "22") (pinfunction "VDDA_22") (pintype "power_in"))
    )
    (net (code "96") (name "/VDDK") (class "Default")
      (node (ref "C20") (pin "2") (pinfunction "2_2") (pintype "passive"))
      (node (ref "C21") (pin "2") (pinfunction "2_2") (pintype "passive"))
      (node (ref "R8") (pin "1") (pinfunction "1_1") (pintype "passive"))
      (node (ref "U2") (pin "40") (pinfunction "VDDK_40") (pintype "power_in"))
    )
    (net (code "97") (name "/VREF+") (class "Default")
      (node (ref "C16") (pin "1") (pinfunction "1_1") (pintype "passive"))
      (node (ref "P7") (pin "18") (pinfunction "18_18") (pintype "passive"))
      (node (ref "R3") (pin "2") (pinfunction "2_2") (pintype "passive"))
      (node (ref "U2") (pin "21") (pinfunction "VREF+_21") (pintype "power_in"))
      (node (ref "VREF1") (pin "1") (pintype "passive"))
    )
    (net (code "98") (name "/X32KI") (class "Default")
      (node (ref "C9") (pin "2") (pinfunction "2_2") (pintype "passive"))
      (node (ref "R13") (pin "2") (pintype "passive"))
      (node (ref "U2") (pin "8") (pinfunction "PC14/OSC32IN_8") (pintype "bidirectional"))
      (node (ref "Y1") (pin "1") (pinfunction "OSC1_1") (pintype "passive"))
    )
    (net (code "99") (name "/X32KO") (class "Default")
      (node (ref "C12") (pin "2") (pinfunction "2_2") (pintype "passive"))
      (node (ref "R14") (pin "2") (pintype "passive"))
      (node (ref "U2") (pin "9") (pinfunction "PC15/OSC32OUT_9") (pintype "bidirectional"))
      (node (ref "Y1") (pin "2") (pinfunction "OSC2_2") (pintype "passive"))
    )
    (net (code "100") (name "/XI") (class "Default")
      (node (ref "C14") (pin "2") (pinfunction "2_2") (pintype "passive"))
      (node (ref "U2") (pin "12") (pinfunction "OSC_IN_12") (pintype "input"))
      (node (ref "Y2") (pin "1") (pinfunction "OSC1_1") (pintype "passive"))
    )
    (net (code "101") (name "/XO") (class "Default")
      (node (ref "C15") (pin "2") (pinfunction "2_2") (pintype "passive"))
      (node (ref "U2") (pin "13") (pinfunction "OSC_OUT_13") (pintype "output"))
      (node (ref "Y2") (pin "3") (pinfunction "OSC2_3") (pintype "passive"))
    )
    (net (code "102") (name "1V2") (class "Default")
      (node (ref "C1") (pin "2") (pinfunction "2_2") (pintype "passive"))
      (node (ref "C2") (pin "2") (pinfunction "2_2") (pintype "passive"))
      (node (ref "L1") (pin "2") (pinfunction "2_2") (pintype "passive"))
      (node (ref "R8") (pin "2") (pinfunction "2_2") (pintype "passive"))
      (node (ref "U1") (pin "6") (pinfunction "FB1V23_6") (pintype "input"))
    )
    (net (code "103") (name "3V3") (class "Default")
      (node (ref "C5") (pin "2") (pinfunction "2_2") (pintype "passive"))
      (node (ref "D3") (pin "1") (pinfunction "A_1") (pintype "passive"))
      (node (ref "LCD1") (pin "6") (pinfunction "VCC_6") (pintype "passive"))
      (node (ref "LCD1") (pin "7") (pinfunction "VCC_7") (pintype "passive"))
      (node (ref "P7") (pin "3") (pinfunction "3_3") (pintype "passive"))
      (node (ref "P8") (pin "1") (pinfunction "1_1") (pintype "passive"))
      (node (ref "P8") (pin "2") (pinfunction "2_2") (pintype "passive"))
      (node (ref "P8") (pin "3") (pinfunction "3_3") (pintype "passive"))
      (node (ref "P8") (pin "4") (pinfunction "4_4") (pintype "passive"))
      (node (ref "P9") (pin "22") (pinfunction "22_22") (pintype "passive"))
      (node (ref "P9") (pin "23") (pinfunction "23_23") (pintype "passive"))
      (node (ref "P9") (pin "24") (pinfunction "24_24") (pintype "passive"))
      (node (ref "R5") (pin "1") (pinfunction "1_1") (pintype "passive"))
      (node (ref "R6") (pin "1") (pinfunction "1_1") (pintype "passive"))
      (node (ref "U1") (pin "5") (pinfunction "LDO_3V3_5") (pintype "power_in"))
    )
    (net (code "104") (name "GND") (class "Default")
      (node (ref "C1") (pin "1") (pinfunction "1_1") (pintype "passive"))
      (node (ref "C10") (pin "1") (pinfunction "1_1") (pintype "passive"))
      (node (ref "C11") (pin "2") (pinfunction "2_2") (pintype "passive"))
      (node (ref "C12") (pin "1") (pinfunction "1_1") (pintype "passive"))
      (node (ref "C13") (pin "2") (pinfunction "2_2") (pintype "passive"))
      (node (ref "C14") (pin "1") (pinfunction "1_1") (pintype "passive"))
      (node (ref "C15") (pin "1") (pinfunction "1_1") (pintype "passive"))
      (node (ref "C16") (pin "2") (pinfunction "2_2") (pintype "passive"))
      (node (ref "C17") (pin "2") (pinfunction "2_2") (pintype "passive"))
      (node (ref "C18") (pin "2") (pinfunction "2_2") (pintype "passive"))
      (node (ref "C19") (pin "1") (pinfunction "1_1") (pintype "passive"))
      (node (ref "C2") (pin "1") (pinfunction "1_1") (pintype "passive"))
      (node (ref "C20") (pin "1") (pinfunction "1_1") (pintype "passive"))
      (node (ref "C21") (pin "1") (pinfunction "1_1") (pintype "passive"))
      (node (ref "C22") (pin "1") (pinfunction "1_1") (pintype "passive"))
      (node (ref "C23") (pin "1") (pinfunction "1_1") (pintype "passive"))
      (node (ref "C26") (pin "1") (pinfunction "1_1") (pintype "passive"))
      (node (ref "C27") (pin "1") (pinfunction "1_1") (pintype "passive"))
      (node (ref "C3") (pin "1") (pinfunction "1_1") (pintype "passive"))
      (node (ref "C34") (pin "2") (pinfunction "2_2") (pintype "passive"))
      (node (ref "C35") (pin "2") (pinfunction "2_2") (pintype "passive"))
      (node (ref "C4") (pin "1") (pinfunction "1_1") (pintype "passive"))
      (node (ref "C5") (pin "1") (pinfunction "1_1") (pintype "passive"))
      (node (ref "C6") (pin "1") (pinfunction "1_1") (pintype "passive"))
      (node (ref "C7") (pin "1") (pinfunction "1_1") (pintype "passive"))
      (node (ref "C8") (pin "2") (pinfunction "2_2") (pintype "passive"))
      (node (ref "C9") (pin "1") (pinfunction "1_1") (pintype "passive"))
      (node (ref "LCD1") (pin "36") (pinfunction "GND_36") (pintype "passive"))
      (node (ref "LCD1") (pin "4") (pinfunction "GLED_4") (pintype "passive"))
      (node (ref "LCD1") (pin "5") (pinfunction "GLED_5") (pintype "passive"))
      (node (ref "P1") (pin "4") (pinfunction "4_4") (pintype "passive"))
      (node (ref "P10") (pin "10") (pintype "passive"))
      (node (ref "P10") (pin "11") (pintype "passive"))
      (node (ref "P10") (pin "8") (pintype "passive"))
      (node (ref "P12") (pin "10") (pinfunction "10_10") (pintype "passive"))
      (node (ref "P12") (pin "11") (pinfunction "11_11") (pintype "passive"))
      (node (ref "P12") (pin "12") (pinfunction "12_12") (pintype "passive"))
      (node (ref "P12") (pin "13") (pinfunction "13_13") (pintype "passive"))
      (node (ref "P12") (pin "14") (pinfunction "14_14") (pintype "passive"))
      (node (ref "P12") (pin "9") (pinfunction "9_9") (pintype "passive"))
      (node (ref "P13") (pin "5") (pinfunction "5_5") (pintype "passive"))
      (node (ref "P13") (pin "6") (pinfunction "6_6") (pintype "passive"))
      (node (ref "P2") (pin "0") (pinfunction "GND_0") (pintype "power_in"))
      (node (ref "P2") (pin "4") (pinfunction "GND_4") (pintype "power_in"))
      (node (ref "P4") (pin "0") (pinfunction "GND_0") (pintype "power_in"))
      (node (ref "P4") (pin "4") (pinfunction "GND_4") (pintype "power_in"))
      (node (ref "P8") (pin "29") (pinfunction "29_29") (pintype "passive"))
      (node (ref "P8") (pin "30") (pinfunction "30_30") (pintype "passive"))
      (node (ref "P9") (pin "27") (pinfunction "27_27") (pintype "passive"))
      (node (ref "P9") (pin "28") (pinfunction "28_28") (pintype "passive"))
      (node (ref "R10") (pin "1") (pintype "passive"))
      (node (ref "R7") (pin "1") (pintype "passive"))
      (node (ref "R9") (pin "2") (pintype "passive"))
      (node (ref "S3") (pin "1") (pinfunction "1_1") (pintype "passive"))
      (node (ref "U1") (pin "2") (pinfunction "GND_2") (pintype "power_in"))
      (node (ref "U2") (pin "10") (pinfunction "VSS_10") (pintype "power_in"))
      (node (ref "U2") (pin "19") (pinfunction "VSSA_19") (pintype "power_in"))
      (node (ref "U2") (pin "20") (pinfunction "VREF-_20") (pintype "power_in"))
      (node (ref "U2") (pin "27") (pinfunction "VSS_27") (pintype "power_in"))
      (node (ref "U2") (pin "41") (pinfunction "VSS_41") (pintype "power_in"))
      (node (ref "U2") (pin "47") (pinfunction "VSS_47") (pintype "power_in"))
      (node (ref "U2") (pin "99") (pinfunction "VSS_99") (pintype "power_in"))
      (node (ref "U5") (pin "1") (pinfunction "GND_1") (pintype "power_in"))
      (node (ref "U6") (pin "1") (pinfunction "GND_1") (pintype "power_in"))
    )
    (net (code "105") (name "Net-(C26-Pad2)") (class "Default")
      (node (ref "C26") (pin "2") (pinfunction "2_2") (pintype "passive"))
      (node (ref "P10") (pin "5") (pintype "passive"))
    )
    (net (code "106") (name "Net-(C27-Pad2)") (class "Default")
      (node (ref "C27") (pin "2") (pinfunction "2_2") (pintype "passive"))
      (node (ref "P10") (pin "4") (pintype "passive"))
    )
    (net (code "107") (name "Net-(D1-A)") (class "Default")
      (node (ref "D1") (pin "1") (pinfunction "A_1") (pintype "passive"))
      (node (ref "R1") (pin "2") (pintype "passive"))
    )
    (net (code "108") (name "Net-(D2-A)") (class "Default")
      (node (ref "D2") (pin "1") (pinfunction "A_1") (pintype "passive"))
      (node (ref "R4") (pin "2") (pintype "passive"))
    )
    (net (code "109") (name "Net-(D3-K)") (class "Default")
      (node (ref "D3") (pin "2") (pinfunction "K_2") (pintype "passive"))
      (node (ref "R9") (pin "1") (pintype "passive"))
    )
    (net (code "110") (name "Net-(P10-Pad9)") (class "Default")
      (node (ref "P10") (pin "9") (pintype "passive"))
      (node (ref "R21") (pin "2") (pintype "passive"))
    )
    (net (code "111") (name "Net-(P10-Pad12)") (class "Default")
      (node (ref "P10") (pin "12") (pintype "passive"))
      (node (ref "R22") (pin "2") (pintype "passive"))
    )
    (net (code "112") (name "Net-(R7-Pad2)") (class "Default")
      (node (ref "R7") (pin "2") (pintype "passive"))
      (node (ref "S2") (pin "2") (pinfunction "2_2") (pintype "passive"))
    )
    (net (code "113") (name "Net-(S1-COMMON)") (class "Default")
      (node (ref "F1") (pin "2") (pinfunction "2_2") (pintype "passive"))
      (node (ref "S1") (pin "1") (pinfunction "COMMON_1") (pintype "passive"))
    )
    (net (code "114") (name "Net-(U1-SW)") (class "Default")
      (node (ref "L1") (pin "1") (pinfunction "1_1") (pintype "passive"))
      (node (ref "U1") (pin "3") (pinfunction "SW_3") (pintype "output"))
    )
    (net (code "115") (name "VBUS") (class "Default")
      (node (ref "C34") (pin "1") (pinfunction "1_1") (pintype "passive"))
      (node (ref "C35") (pin "1") (pinfunction "1_1") (pintype "passive"))
      (node (ref "F1") (pin "1") (pinfunction "1_1") (pintype "passive"))
      (node (ref "P13") (pin "9") (pinfunction "9_9") (pintype "passive"))
      (node (ref "P8") (pin "5") (pinfunction "5_5") (pintype "passive"))
      (node (ref "P8") (pin "6") (pinfunction "6_6") (pintype "passive"))
      (node (ref "P8") (pin "7") (pinfunction "7_7") (pintype "passive"))
      (node (ref "P8") (pin "8") (pinfunction "8_8") (pintype "passive"))
      (node (ref "R45") (pin "1") (pintype "passive"))
      (node (ref "R46") (pin "1") (pintype "passive"))
      (node (ref "U5") (pin "2") (pinfunction "VO-_2") (pintype "power_in"))
      (node (ref "U6") (pin "2") (pinfunction "VO-_2") (pintype "power_in"))
    )
    (net (code "116") (name "VBUS_P1") (class "Default")
      (node (ref "C18") (pin "1") (pinfunction "1_1") (pintype "passive"))
      (node (ref "P4") (pin "1") (pinfunction "+5V_1") (pintype "power_in"))
      (node (ref "R45") (pin "2") (pintype "passive"))
      (node (ref "U5") (pin "3") (pinfunction "VI+_3") (pintype "power_in"))
    )
    (net (code "117") (name "VBUS_P2") (class "Default")
      (node (ref "C11") (pin "1") (pinfunction "1_1") (pintype "passive"))
      (node (ref "P2") (pin "1") (pinfunction "+5V_1") (pintype "power_in"))
      (node (ref "R46") (pin "2") (pintype "passive"))
      (node (ref "U6") (pin "3") (pinfunction "VI+_3") (pintype "power_in"))
    )
    (net (code "118") (name "VDD") (class "Default")
      (node (ref "C13") (pin "1") (pinfunction "1_1") (pintype "passive"))
      (node (ref "C19") (pin "2") (pinfunction "2_2") (pintype "passive"))
      (node (ref "C22") (pin "2") (pinfunction "2_2") (pintype "passive"))
      (node (ref "C23") (pin "2") (pinfunction "2_2") (pintype "passive"))
      (node (ref "C6") (pin "2") (pinfunction "2_2") (pintype "passive"))
      (node (ref "C8") (pin "1") (pinfunction "1_1") (pintype "passive"))
      (node (ref "D4") (pin "2") (pinfunction "K_2") (pintype "passive"))
      (node (ref "P13") (pin "7") (pinfunction "7_7") (pintype "passive"))
      (node (ref "P13") (pin "8") (pinfunction "8_8") (pintype "passive"))
      (node (ref "R1") (pin "1") (pintype "passive"))
      (node (ref "R2") (pin "1") (pintype "passive"))
      (node (ref "R23") (pin "1") (pintype "passive"))
      (node (ref "R4") (pin "1") (pintype "passive"))
      (node (ref "R6") (pin "2") (pinfunction "2_2") (pintype "passive"))
      (node (ref "U2") (pin "100") (pinfunction "VDD_100") (pintype "power_in"))
      (node (ref "U2") (pin "11") (pinfunction "VDD_11") (pintype "power_in"))
      (node (ref "U2") (pin "28") (pinfunction "VDD_28") (pintype "power_in"))
      (node (ref "U2") (pin "46") (pinfunction "VDD_46") (pintype "power_in"))
      (node (ref "U2") (pin "75") (pinfunction "VDD_75") (pintype "power_in"))
    )
    (net (code "119") (name "unconnected-(P10-Pad7)") (class "Default")
      (node (ref "P10") (pin "7") (pintype "passive"))
    )
    (net (code "120") (name "unconnected-(S1-NO-Pad3)") (class "Default")
      (node (ref "S1") (pin "3") (pinfunction "NO_3") (pintype "passive"))
    )
    (net (code "121") (name "unconnected-(U1-NC.-Pad1)") (class "Default")
      (node (ref "U1") (pin "1") (pinfunction "NC._1") (pintype "passive"))
    )
  )
)
